# Absolute_Encoder.net
KiCad netlist of a schematic drawn in Altium Designer
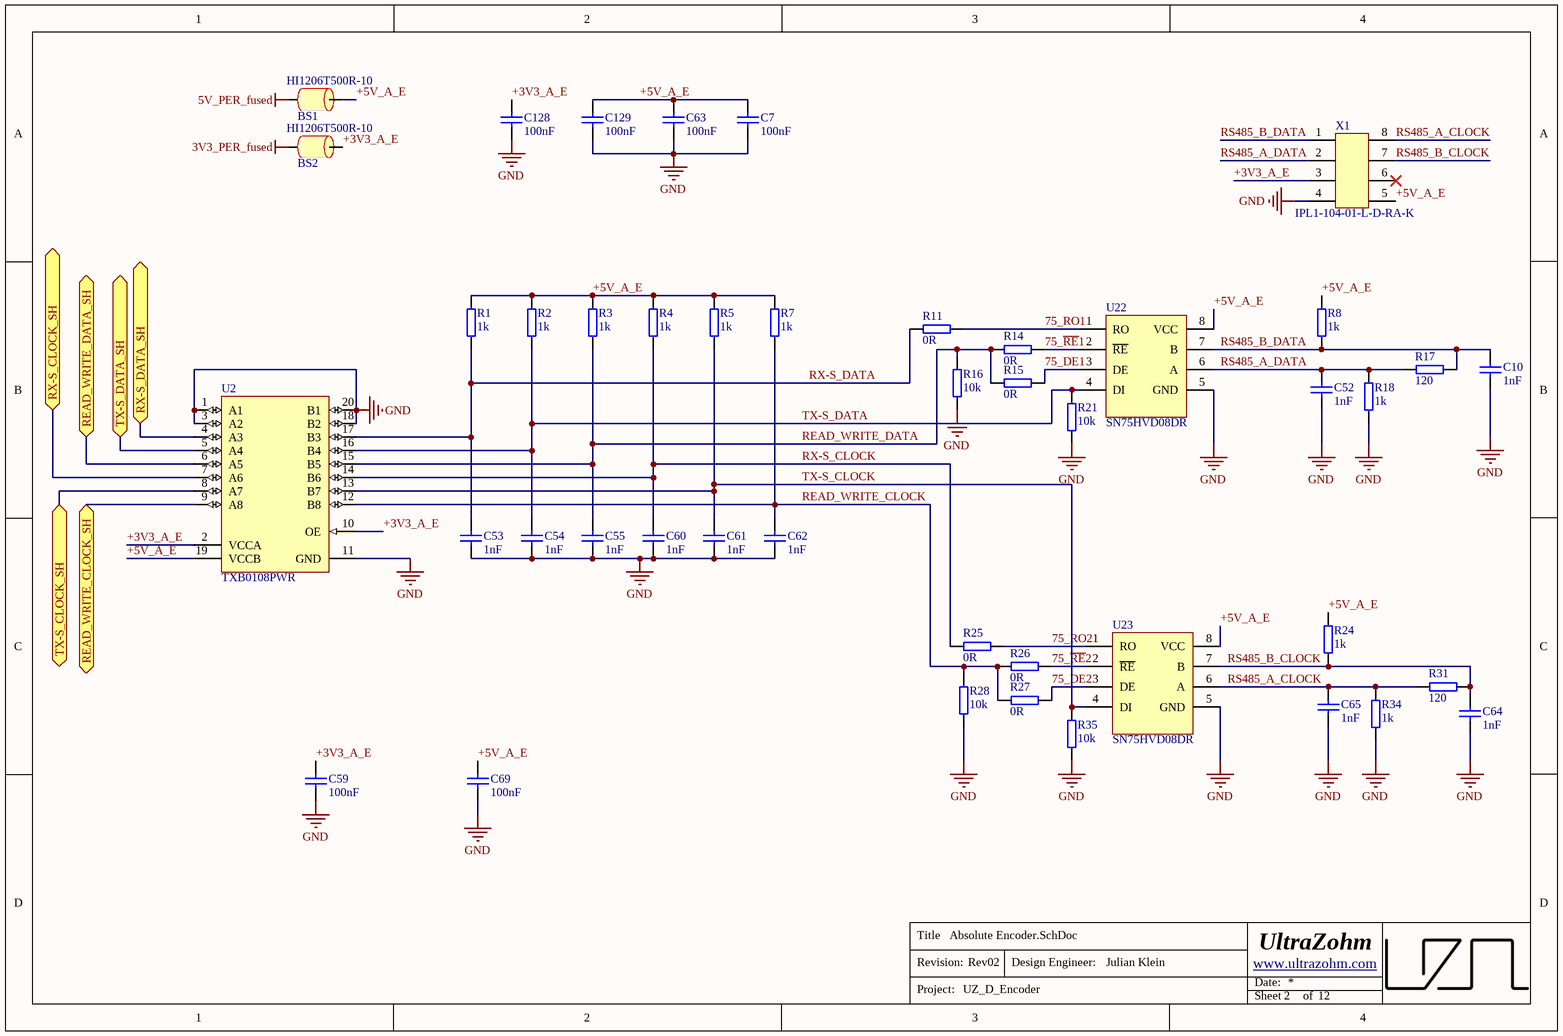
[diagram p0: Absolute Encoder.SchDoc]

(export (version "E")
  (design (tool "Eeschema 10.0.6"))
  (components
    (comp (ref "BS1")
      (value "HI1206T500R-10")
      (footprint "RES_1206")
      (description "Ferrite bead 6A")
      (fields (field (name "MF") "Laird"))
      (libsource (lib "Componentes_SOC") (part "Bead"))
    )
    (comp (ref "BS2")
      (value "HI1206T500R-10")
      (footprint "RES_1206")
      (description "Ferrite bead 6A")
      (fields (field (name "MF") "Laird"))
      (libsource (lib "Componentes_SOC") (part "Bead"))
    )
    (comp (ref "C7")
      (value "100nF")
      (footprint "CAPC1608X07N")
      (fields (field (name "MF") "Würth") (field (name "MPN") "885012206071") (field (name "VOLTAGE") "16V"))
      (libsource (lib "UltraZohm_ADC") (part "Cap_0603"))
    )
    (comp (ref "C10")
      (value "1nF")
      (footprint "CAPC1608X07N")
      (fields (field (name "VOLTAGE") "16V"))
      (libsource (lib "UltraZohm_ADC") (part "Cap_0603"))
    )
    (comp (ref "C52")
      (value "1nF")
      (footprint "CAPC1608X07N")
      (fields (field (name "VOLTAGE") "16V"))
      (libsource (lib "UltraZohm_ADC") (part "Cap_0603"))
    )
    (comp (ref "C53")
      (value "1nF")
      (footprint "CAPC1608X07N")
      (fields (field (name "MF") "Würth") (field (name "MPN") "885012206071") (field (name "VOLTAGE") "25V"))
      (libsource (lib "UltraZohm_ADC") (part "Cap_0603"))
    )
    (comp (ref "C54")
      (value "1nF")
      (footprint "CAPC1608X07N")
      (fields (field (name "MF") "Würth") (field (name "MPN") "885012206071") (field (name "VOLTAGE") "25V"))
      (libsource (lib "UltraZohm_ADC") (part "Cap_0603"))
    )
    (comp (ref "C55")
      (value "1nF")
      (footprint "CAPC1608X07N")
      (fields (field (name "MF") "Würth") (field (name "MPN") "885012206071") (field (name "VOLTAGE") "25V"))
      (libsource (lib "UltraZohm_ADC") (part "Cap_0603"))
    )
    (comp (ref "C59")
      (value "100nF")
      (footprint "CAPC1608X07N")
      (fields (field (name "MF") "Würth") (field (name "MPN") "885012206071") (field (name "VOLTAGE") "25V"))
      (libsource (lib "UltraZohm_ADC") (part "Cap_0603"))
    )
    (comp (ref "C60")
      (value "1nF")
      (footprint "CAPC1608X07N")
      (fields (field (name "MF") "Würth") (field (name "MPN") "885012206071") (field (name "VOLTAGE") "25V"))
      (libsource (lib "UltraZohm_ADC") (part "Cap_0603"))
    )
    (comp (ref "C61")
      (value "1nF")
      (footprint "CAPC1608X07N")
      (fields (field (name "MF") "Würth") (field (name "MPN") "885012206071") (field (name "VOLTAGE") "25V"))
      (libsource (lib "UltraZohm_ADC") (part "Cap_0603"))
    )
    (comp (ref "C62")
      (value "1nF")
      (footprint "CAPC1608X07N")
      (fields (field (name "MF") "Würth") (field (name "MPN") "885012206071") (field (name "VOLTAGE") "25V"))
      (libsource (lib "UltraZohm_ADC") (part "Cap_0603"))
    )
    (comp (ref "C63")
      (value "100nF")
      (footprint "CAPC1608X07N")
      (fields (field (name "MF") "Würth") (field (name "MPN") "885012206071") (field (name "VOLTAGE") "16V"))
      (libsource (lib "UltraZohm_ADC") (part "Cap_0603"))
    )
    (comp (ref "C64")
      (value "1nF")
      (footprint "CAPC1608X07N")
      (fields (field (name "VOLTAGE") "16V"))
      (libsource (lib "UltraZohm_ADC") (part "Cap_0603"))
    )
    (comp (ref "C65")
      (value "1nF")
      (footprint "CAPC1608X07N")
      (fields (field (name "VOLTAGE") "16V"))
      (libsource (lib "UltraZohm_ADC") (part "Cap_0603"))
    )
    (comp (ref "C69")
      (value "100nF")
      (footprint "CAPC1608X07N")
      (fields (field (name "MF") "Würth") (field (name "MPN") "885012206071") (field (name "VOLTAGE") "16V"))
      (libsource (lib "UltraZohm_ADC") (part "Cap_0603"))
    )
    (comp (ref "C128")
      (value "100nF")
      (footprint "CAPC1608X07N")
      (fields (field (name "MF") "Würth") (field (name "MPN") "885012206071") (field (name "VOLTAGE") "25V"))
      (libsource (lib "UltraZohm_ADC") (part "Cap_0603"))
    )
    (comp (ref "C129")
      (value "100nF")
      (footprint "CAPC1608X07N")
      (fields (field (name "MF") "Würth") (field (name "MPN") "885012206071") (field (name "VOLTAGE") "16V"))
      (libsource (lib "UltraZohm_ADC") (part "Cap_0603"))
    )
    (comp (ref "R1")
      (value "1k")
      (footprint "RESC1608X06N")
      (fields (field (name "MF") "Yageo") (field (name "MPN") "RC0603FR-071KL"))
      (libsource (lib "UltraZohm_ADC") (part "R_0603"))
    )
    (comp (ref "R2")
      (value "1k")
      (footprint "RESC1608X06N")
      (fields (field (name "MF") "Yageo") (field (name "MPN") "RC0603FR-071KL"))
      (libsource (lib "UltraZohm_ADC") (part "R_0603"))
    )
    (comp (ref "R3")
      (value "1k")
      (footprint "RESC1608X06N")
      (fields (field (name "MF") "Yageo") (field (name "MPN") "RC0603FR-071KL"))
      (libsource (lib "UltraZohm_ADC") (part "R_0603"))
    )
    (comp (ref "R4")
      (value "1k")
      (footprint "RESC1608X06N")
      (fields (field (name "MF") "Yageo") (field (name "MPN") "RC0603FR-071KL"))
      (libsource (lib "UltraZohm_ADC") (part "R_0603"))
    )
    (comp (ref "R5")
      (value "1k")
      (footprint "RESC1608X06N")
      (fields (field (name "MF") "Yageo") (field (name "MPN") "RC0603FR-071KL"))
      (libsource (lib "UltraZohm_ADC") (part "R_0603"))
    )
    (comp (ref "R7")
      (value "1k")
      (footprint "RESC1608X06N")
      (fields (field (name "MF") "Yageo") (field (name "MPN") "RC0603FR-071KL"))
      (libsource (lib "UltraZohm_ADC") (part "R_0603"))
    )
    (comp (ref "R8")
      (value "1k")
      (footprint "RESC1608X06N")
      (fields (field (name "MF") "Yageo") (field (name "MPN") "RC0603FR-071KL"))
      (libsource (lib "UltraZohm_ADC") (part "R_0603"))
    )
    (comp (ref "R11")
      (value "0R")
      (footprint "RESC1608X06N")
      (fields (field (name "MF") "Vishay") (field (name "MPN") "CRCW06030000Z0EAC"))
      (libsource (lib "UltraZohm_ADC") (part "R_0603"))
    )
    (comp (ref "R14")
      (value "0R")
      (footprint "RESC1608X06N")
      (fields (field (name "MF") "Vishay") (field (name "MPN") "CRCW06030000Z0EAC"))
      (libsource (lib "UltraZohm_ADC") (part "R_0603"))
    )
    (comp (ref "R15")
      (value "0R")
      (footprint "RESC1608X06N")
      (fields (field (name "MF") "Vishay") (field (name "MPN") "CRCW06030000Z0EAC"))
      (libsource (lib "UltraZohm_ADC") (part "R_0603"))
    )
    (comp (ref "R16")
      (value "10k")
      (footprint "RESC1608X06N")
      (fields (field (name "MF") "Vishay") (field (name "MPN") "CRCW06030000Z0EAC"))
      (libsource (lib "UltraZohm_ADC") (part "R_0603"))
    )
    (comp (ref "R17")
      (value "120")
      (footprint "RESC1608X06N")
      (libsource (lib "UltraZohm_ADC") (part "R_0603"))
    )
    (comp (ref "R18")
      (value "1k")
      (footprint "RESC1608X06N")
      (fields (field (name "MF") "Yageo") (field (name "MPN") "RC0603FR-071KL"))
      (libsource (lib "UltraZohm_ADC") (part "R_0603"))
    )
    (comp (ref "R21")
      (value "10k")
      (footprint "RESC1608X06N")
      (fields (field (name "MF") "Vishay") (field (name "MPN") "CRCW06030000Z0EAC"))
      (libsource (lib "UltraZohm_ADC") (part "R_0603"))
    )
    (comp (ref "R24")
      (value "1k")
      (footprint "RESC1608X06N")
      (fields (field (name "MF") "Yageo") (field (name "MPN") "RC0603FR-071KL"))
      (libsource (lib "UltraZohm_ADC") (part "R_0603"))
    )
    (comp (ref "R25")
      (value "0R")
      (footprint "RESC1608X06N")
      (fields (field (name "MF") "Vishay") (field (name "MPN") "CRCW06030000Z0EAC"))
      (libsource (lib "UltraZohm_ADC") (part "R_0603"))
    )
    (comp (ref "R26")
      (value "0R")
      (footprint "RESC1608X06N")
      (fields (field (name "MF") "Vishay") (field (name "MPN") "CRCW06030000Z0EAC"))
      (libsource (lib "UltraZohm_ADC") (part "R_0603"))
    )
    (comp (ref "R27")
      (value "0R")
      (footprint "RESC1608X06N")
      (fields (field (name "MF") "Vishay") (field (name "MPN") "CRCW06030000Z0EAC"))
      (libsource (lib "UltraZohm_ADC") (part "R_0603"))
    )
    (comp (ref "R28")
      (value "10k")
      (footprint "RESC1608X06N")
      (fields (field (name "MF") "Vishay") (field (name "MPN") "CRCW06030000Z0EAC"))
      (libsource (lib "UltraZohm_ADC") (part "R_0603"))
    )
    (comp (ref "R31")
      (value "120")
      (footprint "RESC1608X06N")
      (libsource (lib "UltraZohm_ADC") (part "R_0603"))
    )
    (comp (ref "R34")
      (value "1k")
      (footprint "RESC1608X06N")
      (fields (field (name "MF") "Yageo") (field (name "MPN") "RC0603FR-071KL"))
      (libsource (lib "UltraZohm_ADC") (part "R_0603"))
    )
    (comp (ref "R35")
      (value "10k")
      (footprint "RESC1608X06N")
      (fields (field (name "MF") "Vishay") (field (name "MPN") "CRCW06030000Z0EAC"))
      (libsource (lib "UltraZohm_ADC") (part "R_0603"))
    )
    (comp (ref "U2")
      (value "TXB0108PWR")
      (footprint "PW0020A_L")
      (fields (field (name "MANUFACTURER") "Texas Instruments"))
      (libsource (lib "Altium Content Vault") (part "TI-TXB0108-PW-20"))
    )
    (comp (ref "U22")
      (value "SN75HVD08DR")
      (footprint "SOIC8_N")
      (description "IC TRANSCEIVER HALF 1/1 8SOIC")
      (fields (field (name "MF") "Texas Instruments"))
      (libsource (lib "Componentes_SOC") (part "Transmisor RS485"))
    )
    (comp (ref "U23")
      (value "SN75HVD08DR")
      (footprint "SOIC8_N")
      (description "IC TRANSCEIVER HALF 1/1 8SOIC")
      (fields (field (name "MF") "Texas Instruments"))
      (libsource (lib "Componentes_SOC") (part "Transmisor RS485"))
    )
    (comp (ref "X1")
      (value "IPL1-104-01-L-D-RA-K")
      (footprint "Conector 4x2 TH Horizontal")
      (description "CONN HEADER R/A 8POS 2.54MM Through Hole")
      (fields (field (name "MF") "Samtec"))
      (libsource (lib "Componentes_SOC") (part "Conector 4x2 Horizontal"))
    )
  )
  (nets
    (net (code "1") (name "/+3V3_A_E") (class "Default")
      (node (ref "BS2") (pin "1") (pintype "passive"))
      (node (ref "C128") (pin "1") (pinfunction "1_1") (pintype "passive"))
      (node (ref "C59") (pin "1") (pinfunction "1_1") (pintype "passive"))
      (node (ref "U2") (pin "10") (pinfunction "OE_10") (pintype "input"))
      (node (ref "U2") (pin "2") (pinfunction "VCCA_2") (pintype "power_in"))
      (node (ref "X1") (pin "3") (pintype "passive"))
    )
    (net (code "2") (name "/+5V_A_E") (class "Default")
      (node (ref "BS1") (pin "1") (pintype "passive"))
      (node (ref "C129") (pin "1") (pinfunction "1_1") (pintype "passive"))
      (node (ref "C63") (pin "1") (pinfunction "1_1") (pintype "passive"))
      (node (ref "C69") (pin "1") (pinfunction "1_1") (pintype "passive"))
      (node (ref "C7") (pin "1") (pinfunction "1_1") (pintype "passive"))
      (node (ref "R1") (pin "2") (pintype "passive"))
      (node (ref "R2") (pin "2") (pintype "passive"))
      (node (ref "R24") (pin "2") (pintype "passive"))
      (node (ref "R3") (pin "2") (pintype "passive"))
      (node (ref "R4") (pin "2") (pintype "passive"))
      (node (ref "R5") (pin "2") (pintype "passive"))
      (node (ref "R7") (pin "2") (pintype "passive"))
      (node (ref "R8") (pin "2") (pintype "passive"))
      (node (ref "U2") (pin "19") (pinfunction "VCCB_19") (pintype "power_in"))
      (node (ref "U22") (pin "8") (pinfunction "VCC_8") (pintype "passive"))
      (node (ref "U23") (pin "8") (pinfunction "VCC_8") (pintype "passive"))
      (node (ref "X1") (pin "5") (pintype "passive"))
    )
    (net (code "3") (name "/75_DE1") (class "Default")
      (node (ref "R15") (pin "2") (pintype "passive"))
      (node (ref "U22") (pin "3") (pinfunction "DE_3") (pintype "passive"))
    )
    (net (code "4") (name "/75_DE2") (class "Default")
      (node (ref "R27") (pin "2") (pintype "passive"))
      (node (ref "U23") (pin "3") (pinfunction "DE_3") (pintype "passive"))
    )
    (net (code "5") (name "/75_RO1") (class "Default")
      (node (ref "R11") (pin "2") (pintype "passive"))
      (node (ref "U22") (pin "1") (pinfunction "RO_1") (pintype "passive"))
    )
    (net (code "6") (name "/75_RO2") (class "Default")
      (node (ref "R25") (pin "2") (pintype "passive"))
      (node (ref "U23") (pin "1") (pinfunction "RO_1") (pintype "passive"))
    )
    (net (code "7") (name "/75_~{RE}1") (class "Default")
      (node (ref "R14") (pin "2") (pintype "passive"))
      (node (ref "U22") (pin "2") (pinfunction "~{RE}_2") (pintype "passive"))
    )
    (net (code "8") (name "/75_~{RE}2") (class "Default")
      (node (ref "R26") (pin "2") (pintype "passive"))
      (node (ref "U23") (pin "2") (pinfunction "~{RE}_2") (pintype "passive"))
    )
    (net (code "9") (name "/READ_WRITE_CLOCK") (class "Default")
      (node (ref "C62") (pin "1") (pinfunction "1_1") (pintype "passive"))
      (node (ref "R26") (pin "1") (pintype "passive"))
      (node (ref "R27") (pin "1") (pintype "passive"))
      (node (ref "R28") (pin "2") (pintype "passive"))
      (node (ref "R7") (pin "1") (pintype "passive"))
      (node (ref "U2") (pin "12") (pinfunction "B8_12") (pintype "bidirectional"))
    )
    (net (code "10") (name "/READ_WRITE_CLOCK_SH") (class "Default")
      (node (ref "U2") (pin "9") (pinfunction "A8_9") (pintype "bidirectional"))
    )
    (net (code "11") (name "/READ_WRITE_DATA") (class "Default")
      (node (ref "C55") (pin "1") (pinfunction "1_1") (pintype "passive"))
      (node (ref "R14") (pin "1") (pintype "passive"))
      (node (ref "R15") (pin "1") (pintype "passive"))
      (node (ref "R16") (pin "2") (pintype "passive"))
      (node (ref "R3") (pin "1") (pintype "passive"))
      (node (ref "U2") (pin "15") (pinfunction "B5_15") (pintype "bidirectional"))
    )
    (net (code "12") (name "/READ_WRITE_DATA_SH") (class "Default")
      (node (ref "U2") (pin "6") (pinfunction "A5_6") (pintype "bidirectional"))
    )
    (net (code "13") (name "/RS485_A_CLOCK") (class "Default")
      (node (ref "C65") (pin "1") (pinfunction "1_1") (pintype "passive"))
      (node (ref "R31") (pin "2") (pintype "passive"))
      (node (ref "R34") (pin "2") (pintype "passive"))
      (node (ref "U23") (pin "6") (pinfunction "A_6") (pintype "passive"))
      (node (ref "X1") (pin "8") (pintype "passive"))
    )
    (net (code "14") (name "/RS485_A_DATA") (class "Default")
      (node (ref "C52") (pin "1") (pinfunction "1_1") (pintype "passive"))
      (node (ref "R17") (pin "2") (pintype "passive"))
      (node (ref "R18") (pin "2") (pintype "passive"))
      (node (ref "U22") (pin "6") (pinfunction "A_6") (pintype "passive"))
      (node (ref "X1") (pin "2") (pintype "passive"))
    )
    (net (code "15") (name "/RS485_B_CLOCK") (class "Default")
      (node (ref "C64") (pin "1") (pinfunction "1_1") (pintype "passive"))
      (node (ref "R24") (pin "1") (pintype "passive"))
      (node (ref "R31") (pin "1") (pintype "passive"))
      (node (ref "U23") (pin "7") (pinfunction "B_7") (pintype "passive"))
      (node (ref "X1") (pin "7") (pintype "passive"))
    )
    (net (code "16") (name "/RS485_B_DATA") (class "Default")
      (node (ref "C10") (pin "1") (pinfunction "1_1") (pintype "passive"))
      (node (ref "R17") (pin "1") (pintype "passive"))
      (node (ref "R8") (pin "1") (pintype "passive"))
      (node (ref "U22") (pin "7") (pinfunction "B_7") (pintype "passive"))
      (node (ref "X1") (pin "1") (pintype "passive"))
    )
    (net (code "17") (name "/RX-S_CLOCK") (class "Default")
      (node (ref "C60") (pin "1") (pinfunction "1_1") (pintype "passive"))
      (node (ref "R25") (pin "1") (pintype "passive"))
      (node (ref "R4") (pin "1") (pintype "passive"))
      (node (ref "U2") (pin "14") (pinfunction "B6_14") (pintype "bidirectional"))
    )
    (net (code "18") (name "/RX-S_CLOCK_SH") (class "Default")
      (node (ref "U2") (pin "7") (pinfunction "A6_7") (pintype "bidirectional"))
    )
    (net (code "19") (name "/RX-S_DATA") (class "Default")
      (node (ref "C53") (pin "1") (pinfunction "1_1") (pintype "passive"))
      (node (ref "R1") (pin "1") (pintype "passive"))
      (node (ref "R11") (pin "1") (pintype "passive"))
      (node (ref "U2") (pin "17") (pinfunction "B3_17") (pintype "bidirectional"))
    )
    (net (code "20") (name "/RX-S_DATA_SH") (class "Default")
      (node (ref "U2") (pin "4") (pinfunction "A3_4") (pintype "bidirectional"))
    )
    (net (code "21") (name "/TX-S_CLOCK") (class "Default")
      (node (ref "C61") (pin "1") (pinfunction "1_1") (pintype "passive"))
      (node (ref "R35") (pin "2") (pintype "passive"))
      (node (ref "R5") (pin "1") (pintype "passive"))
      (node (ref "U2") (pin "13") (pinfunction "B7_13") (pintype "bidirectional"))
      (node (ref "U23") (pin "4") (pinfunction "DI_4") (pintype "passive"))
    )
    (net (code "22") (name "/TX-S_CLOCK_SH") (class "Default")
      (node (ref "U2") (pin "8") (pinfunction "A7_8") (pintype "bidirectional"))
    )
    (net (code "23") (name "/TX-S_DATA") (class "Default")
      (node (ref "C54") (pin "1") (pinfunction "1_1") (pintype "passive"))
      (node (ref "R2") (pin "1") (pintype "passive"))
      (node (ref "R21") (pin "2") (pintype "passive"))
      (node (ref "U2") (pin "16") (pinfunction "B4_16") (pintype "bidirectional"))
      (node (ref "U22") (pin "4") (pinfunction "DI_4") (pintype "passive"))
    )
    (net (code "24") (name "/TX-S_DATA_SH") (class "Default")
      (node (ref "U2") (pin "5") (pinfunction "A4_5") (pintype "bidirectional"))
    )
    (net (code "25") (name "3V3_PER_fused") (class "Default")
      (node (ref "BS2") (pin "2") (pintype "passive"))
    )
    (net (code "26") (name "5V_PER_fused") (class "Default") (node (ref "BS1") (pin "2") (pintype "passive")))
    (net (code "27") (name "GND") (class "Default")
      (node (ref "C10") (pin "2") (pinfunction "2_2") (pintype "passive"))
      (node (ref "C128") (pin "2") (pinfunction "2_2") (pintype "passive"))
      (node (ref "C129") (pin "2") (pinfunction "2_2") (pintype "passive"))
      (node (ref "C52") (pin "2") (pinfunction "2_2") (pintype "passive"))
      (node (ref "C53") (pin "2") (pinfunction "2_2") (pintype "passive"))
      (node (ref "C54") (pin "2") (pinfunction "2_2") (pintype "passive"))
      (node (ref "C55") (pin "2") (pinfunction "2_2") (pintype "passive"))
      (node (ref "C59") (pin "2") (pinfunction "2_2") (pintype "passive"))
      (node (ref "C60") (pin "2") (pinfunction "2_2") (pintype "passive"))
      (node (ref "C61") (pin "2") (pinfunction "2_2") (pintype "passive"))
      (node (ref "C62") (pin "2") (pinfunction "2_2") (pintype "passive"))
      (node (ref "C63") (pin "2") (pinfunction "2_2") (pintype "passive"))
      (node (ref "C64") (pin "2") (pinfunction "2_2") (pintype "passive"))
      (node (ref "C65") (pin "2") (pinfunction "2_2") (pintype "passive"))
      (node (ref "C69") (pin "2") (pinfunction "2_2") (pintype "passive"))
      (node (ref "C7") (pin "2") (pinfunction "2_2") (pintype "passive"))
      (node (ref "R16") (pin "1") (pintype "passive"))
      (node (ref "R18") (pin "1") (pintype "passive"))
      (node (ref "R21") (pin "1") (pintype "passive"))
      (node (ref "R28") (pin "1") (pintype "passive"))
      (node (ref "R34") (pin "1") (pintype "passive"))
      (node (ref "R35") (pin "1") (pintype "passive"))
      (node (ref "U2") (pin "1") (pinfunction "A1_1") (pintype "bidirectional"))
      (node (ref "U2") (pin "11") (pinfunction "GND_11") (pintype "power_in"))
      (node (ref "U2") (pin "18") (pinfunction "B2_18") (pintype "bidirectional"))
      (node (ref "U2") (pin "20") (pinfunction "B1_20") (pintype "bidirectional"))
      (node (ref "U2") (pin "3") (pinfunction "A2_3") (pintype "bidirectional"))
      (node (ref "U22") (pin "5") (pinfunction "GND_5") (pintype "passive"))
      (node (ref "U23") (pin "5") (pinfunction "GND_5") (pintype "passive"))
      (node (ref "X1") (pin "4") (pintype "passive"))
    )
    (net (code "28") (name "unconnected-(X1-Pad6)") (class "Default")
      (node (ref "X1") (pin "6") (pintype "passive+no_connect"))
    )
  )
)
